# R_le_Mod_l_Tek.net
KiCad netlist of a schematic drawn in EAGLE
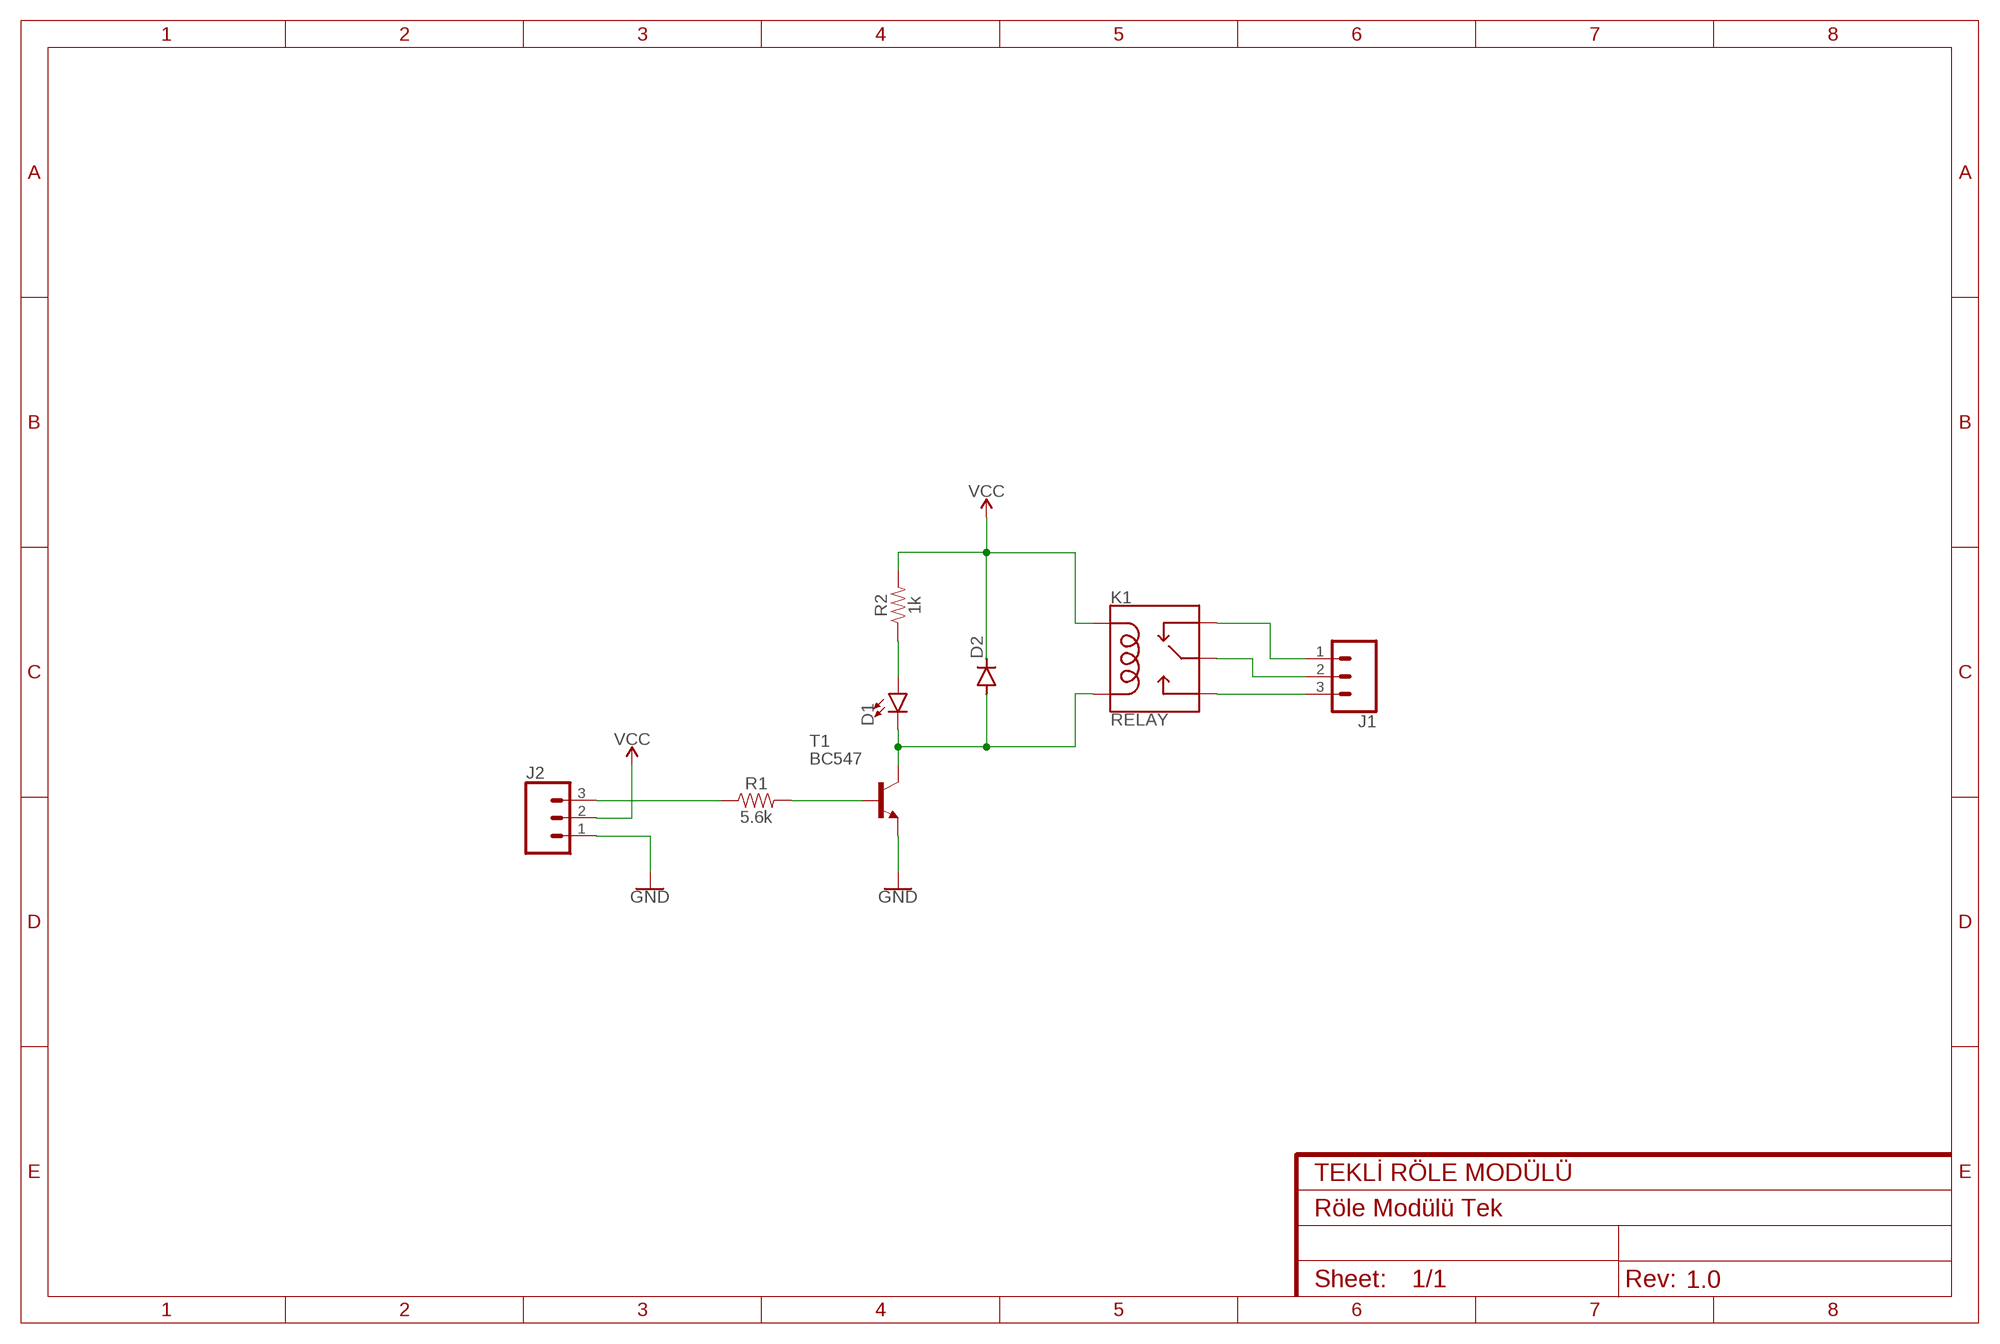
[diagram p0: schematic, sheet 1]

(export (version "E")
  (design (tool "Eeschema 10.0.6"))
  (components
    (comp (ref "D1")
      (value "LED3MM")
      (footprint "eagle-import:LED_3MM")
      (libsource (lib "eagle-import") (part "LED3MM"))
    )
    (comp (ref "D2")
      (value "DIODE-DO07")
      (footprint "eagle-import:DO07")
      (libsource (lib "eagle-import") (part "DIODE-DO07"))
    )
    (comp (ref "J1")
      (value "CONN_03")
      (footprint "eagle-import:1X03")
      (libsource (lib "eagle-import") (part "CONN_03"))
    )
    (comp (ref "J2")
      (value "CONN_03")
      (footprint "eagle-import:1X03")
      (libsource (lib "eagle-import") (part "CONN_03"))
    )
    (comp (ref "K1")
      (value "RELAY")
      (footprint "eagle-import:RELAY-JZC")
      (libsource (lib "eagle-import") (part "RELAY-SPDT-JZC-11F"))
    )
    (comp (ref "R1")
      (value "5.6k")
      (footprint "eagle-import:AXIAL-0.3")
      (libsource (lib "eagle-import") (part "1KOHM-HORIZ-1/4W-1%"))
    )
    (comp (ref "R2")
      (value "1k")
      (footprint "eagle-import:AXIAL-0.3")
      (libsource (lib "eagle-import") (part "1KOHM-HORIZ-1/4W-1%"))
    )
    (comp (ref "T1")
      (value "BC547")
      (footprint "eagle-import:TO92")
      (libsource (lib "eagle-import") (part "BC547"))
    )
  )
  (nets
    (net (code "1") (name "GND") (class "Default")
      (node (ref "J2") (pin "1") (pinfunction "1_1") (pintype "passive"))
      (node (ref "T1") (pin "1") (pinfunction "E_1") (pintype "passive"))
    )
    (net (code "2") (name "Net-(D1-C)") (class "Default")
      (node (ref "D1") (pin "K") (pinfunction "C_K") (pintype "passive"))
      (node (ref "D2") (pin "A") (pinfunction "A_A") (pintype "passive"))
      (node (ref "K1") (pin "1") (pinfunction "COIL2_1") (pintype "bidirectional"))
      (node (ref "T1") (pin "3") (pinfunction "C_3") (pintype "passive"))
    )
    (net (code "3") (name "Net-(K1-MAIN)") (class "Default")
      (node (ref "J1") (pin "2") (pinfunction "2_2") (pintype "passive"))
      (node (ref "K1") (pin "4") (pinfunction "MAIN_4") (pintype "bidirectional"))
    )
    (net (code "4") (name "Net-(K1-NC)") (class "Default")
      (node (ref "J1") (pin "1") (pinfunction "1_1") (pintype "passive"))
      (node (ref "K1") (pin "2") (pinfunction "NC_2") (pintype "bidirectional"))
    )
    (net (code "5") (name "Net-(K1-NO)") (class "Default")
      (node (ref "J1") (pin "3") (pinfunction "3_3") (pintype "passive"))
      (node (ref "K1") (pin "3") (pinfunction "NO_3") (pintype "bidirectional"))
    )
    (net (code "6") (name "Net-(R1-1)") (class "Default")
      (node (ref "J2") (pin "3") (pinfunction "3_3") (pintype "passive"))
      (node (ref "R1") (pin "P$1") (pinfunction "1_P$1") (pintype "passive"))
    )
    (net (code "7") (name "Net-(R1-2)") (class "Default")
      (node (ref "R1") (pin "P$2") (pinfunction "2_P$2") (pintype "passive"))
      (node (ref "T1") (pin "2") (pinfunction "B_2") (pintype "passive"))
    )
    (net (code "8") (name "Net-(R2-1)") (class "Default")
      (node (ref "D1") (pin "A") (pinfunction "A_A") (pintype "passive"))
      (node (ref "R2") (pin "P$1") (pinfunction "1_P$1") (pintype "passive"))
    )
    (net (code "9") (name "VCC") (class "Default")
      (node (ref "D2") (pin "C") (pinfunction "C_C") (pintype "passive"))
      (node (ref "J2") (pin "2") (pinfunction "2_2") (pintype "passive"))
      (node (ref "K1") (pin "5") (pinfunction "COIL1_5") (pintype "bidirectional"))
      (node (ref "R2") (pin "P$2") (pinfunction "2_P$2") (pintype "passive"))
    )
  )
)
